# Channel.net
KiCad netlist of a schematic drawn in Altium Designer
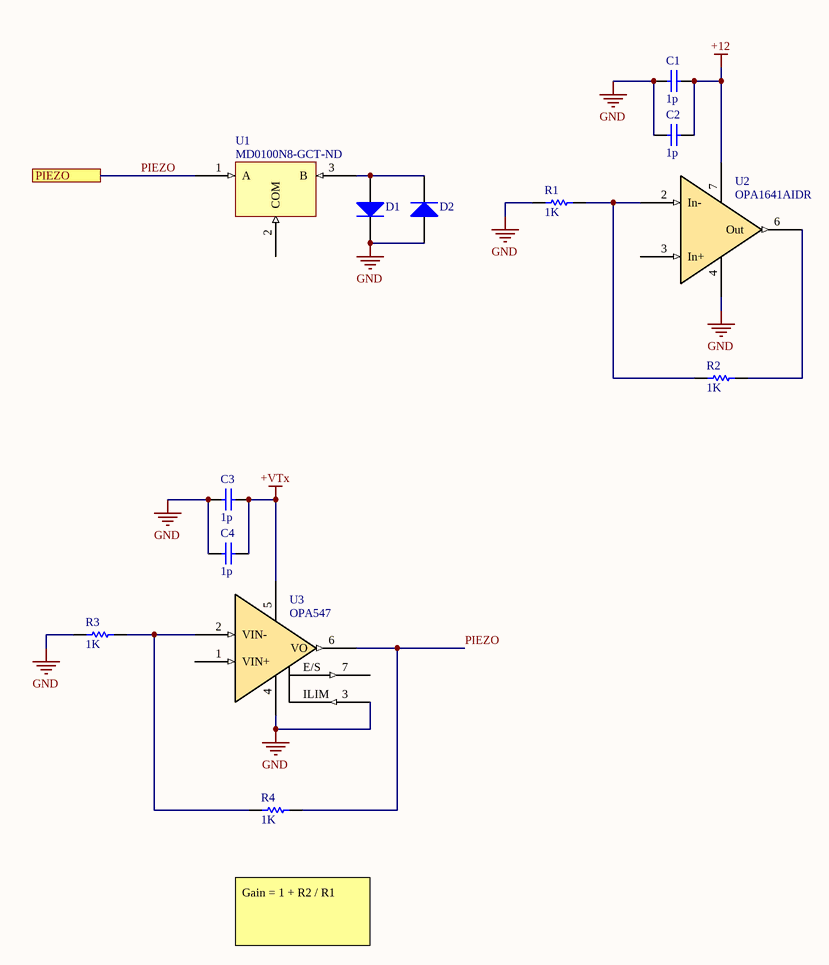
[diagram p0: Channel.SchDoc]

(export (version "E")
  (design (tool "Eeschema 10.0.6"))
  (components
    (comp (ref "C1")
      (value "1p")
      (description "Capacitor")
      (libsource (lib "Simulation Generic Components") (part "Capacitor"))
    )
    (comp (ref "C2")
      (value "1p")
      (description "Capacitor")
      (libsource (lib "Simulation Generic Components") (part "Capacitor"))
    )
    (comp (ref "C3")
      (value "1p")
      (description "Capacitor")
      (libsource (lib "Simulation Generic Components") (part "Capacitor"))
    )
    (comp (ref "C4")
      (value "1p")
      (description "Capacitor")
      (libsource (lib "Simulation Generic Components") (part "Capacitor"))
    )
    (comp (ref "D1") (value "Diode") (libsource (lib "Simulation Generic Components") (part "Diode")))
    (comp (ref "D2") (value "Diode") (libsource (lib "Simulation Generic Components") (part "Diode")))
    (comp (ref "R1")
      (value "1K")
      (description "Resistor")
      (libsource (lib "Simulation Generic Components") (part "Resistor"))
    )
    (comp (ref "R2")
      (value "1K")
      (description "Resistor")
      (libsource (lib "Simulation Generic Components") (part "Resistor"))
    )
    (comp (ref "R3")
      (value "1K")
      (description "Resistor")
      (libsource (lib "Simulation Generic Components") (part "Resistor"))
    )
    (comp (ref "R4")
      (value "1K")
      (description "Resistor")
      (libsource (lib "Simulation Generic Components") (part "Resistor"))
    )
    (comp (ref "U1")
      (value "MD0100N8-GCT-ND")
      (description "T/R Switch")
      (libsource (lib "Tauv-Lib") (part "MD0100N8-GCT-ND"))
    )
    (comp (ref "U2")
      (value "OPA1641AIDR")
      (description "JFET-input audio op-amp, 1 channel")
      (libsource (lib "Tauv-Lib") (part "OPA1641AIDR"))
    )
    (comp (ref "U3")
      (value "OPA547")
      (description "High-voltage, high-current op-amp")
      (libsource (lib "Tauv-Lib") (part "OPA547"))
    )
  )
  (nets
    (net (code "1") (name "+12") (class "Default")
      (node (ref "C1") (pin "2") (pinfunction "2_2") (pintype "passive"))
      (node (ref "C2") (pin "2") (pinfunction "2_2") (pintype "passive"))
      (node (ref "U2") (pin "7") (pinfunction "V+_7") (pintype "power_in"))
    )
    (net (code "2") (name "+VTx") (class "Default")
      (node (ref "C3") (pin "2") (pinfunction "2_2") (pintype "passive"))
      (node (ref "C4") (pin "2") (pinfunction "2_2") (pintype "passive"))
      (node (ref "U3") (pin "5") (pinfunction "V+_5") (pintype "power_in"))
    )
    (net (code "3") (name "/PIEZO") (class "Default")
      (node (ref "R4") (pin "2") (pinfunction "2_2") (pintype "passive"))
      (node (ref "U1") (pin "1") (pinfunction "A_1") (pintype "input"))
      (node (ref "U3") (pin "6") (pinfunction "VO_6") (pintype "output"))
    )
    (net (code "4") (name "GND") (class "Default")
      (node (ref "C1") (pin "1") (pinfunction "1_1") (pintype "passive"))
      (node (ref "C2") (pin "1") (pinfunction "1_1") (pintype "passive"))
      (node (ref "C3") (pin "1") (pinfunction "1_1") (pintype "passive"))
      (node (ref "C4") (pin "1") (pinfunction "1_1") (pintype "passive"))
      (node (ref "D1") (pin "2") (pinfunction "K_2") (pintype "passive"))
      (node (ref "D2") (pin "1") (pinfunction "A_1") (pintype "passive"))
      (node (ref "R1") (pin "2") (pinfunction "2_2") (pintype "passive"))
      (node (ref "R3") (pin "2") (pinfunction "2_2") (pintype "passive"))
      (node (ref "U2") (pin "4") (pinfunction "V-_4") (pintype "power_in"))
      (node (ref "U3") (pin "3") (pinfunction "ILIM_3") (pintype "input"))
      (node (ref "U3") (pin "4") (pinfunction "V-_4") (pintype "power_in"))
    )
    (net (code "5") (name "Net-(D1-A)") (class "Default")
      (node (ref "D1") (pin "1") (pinfunction "A_1") (pintype "passive"))
      (node (ref "D2") (pin "2") (pinfunction "K_2") (pintype "passive"))
      (node (ref "U1") (pin "3") (pinfunction "B_3") (pintype "input"))
    )
    (net (code "6") (name "Net-(U2-In-)") (class "Default")
      (node (ref "R1") (pin "1") (pinfunction "1_1") (pintype "passive"))
      (node (ref "R2") (pin "2") (pinfunction "2_2") (pintype "passive"))
      (node (ref "U2") (pin "2") (pinfunction "In-_2") (pintype "input"))
    )
    (net (code "7") (name "Net-(U2-Out)") (class "Default")
      (node (ref "R2") (pin "1") (pinfunction "1_1") (pintype "passive"))
      (node (ref "U2") (pin "6") (pinfunction "Out_6") (pintype "output"))
    )
    (net (code "8") (name "Net-(U3-VIN-)") (class "Default")
      (node (ref "R3") (pin "1") (pinfunction "1_1") (pintype "passive"))
      (node (ref "R4") (pin "1") (pinfunction "1_1") (pintype "passive"))
      (node (ref "U3") (pin "2") (pinfunction "VIN-_2") (pintype "input"))
    )
    (net (code "9") (name "unconnected-(U1-COM-Pad2)") (class "Default")
      (node (ref "U1") (pin "2") (pinfunction "COM_2") (pintype "input"))
    )
    (net (code "10") (name "unconnected-(U2-In+-Pad3)") (class "Default")
      (node (ref "U2") (pin "3") (pinfunction "In+_3") (pintype "input"))
    )
    (net (code "11") (name "unconnected-(U3-E{slash}S-Pad7)") (class "Default")
      (node (ref "U3") (pin "7") (pinfunction "E/S_7") (pintype "output"))
    )
    (net (code "12") (name "unconnected-(U3-VIN+-Pad1)") (class "Default")
      (node (ref "U3") (pin "1") (pinfunction "VIN+_1") (pintype "input"))
    )
  )
)
